# RFmodule.net
KiCad netlist of a schematic drawn in EAGLE
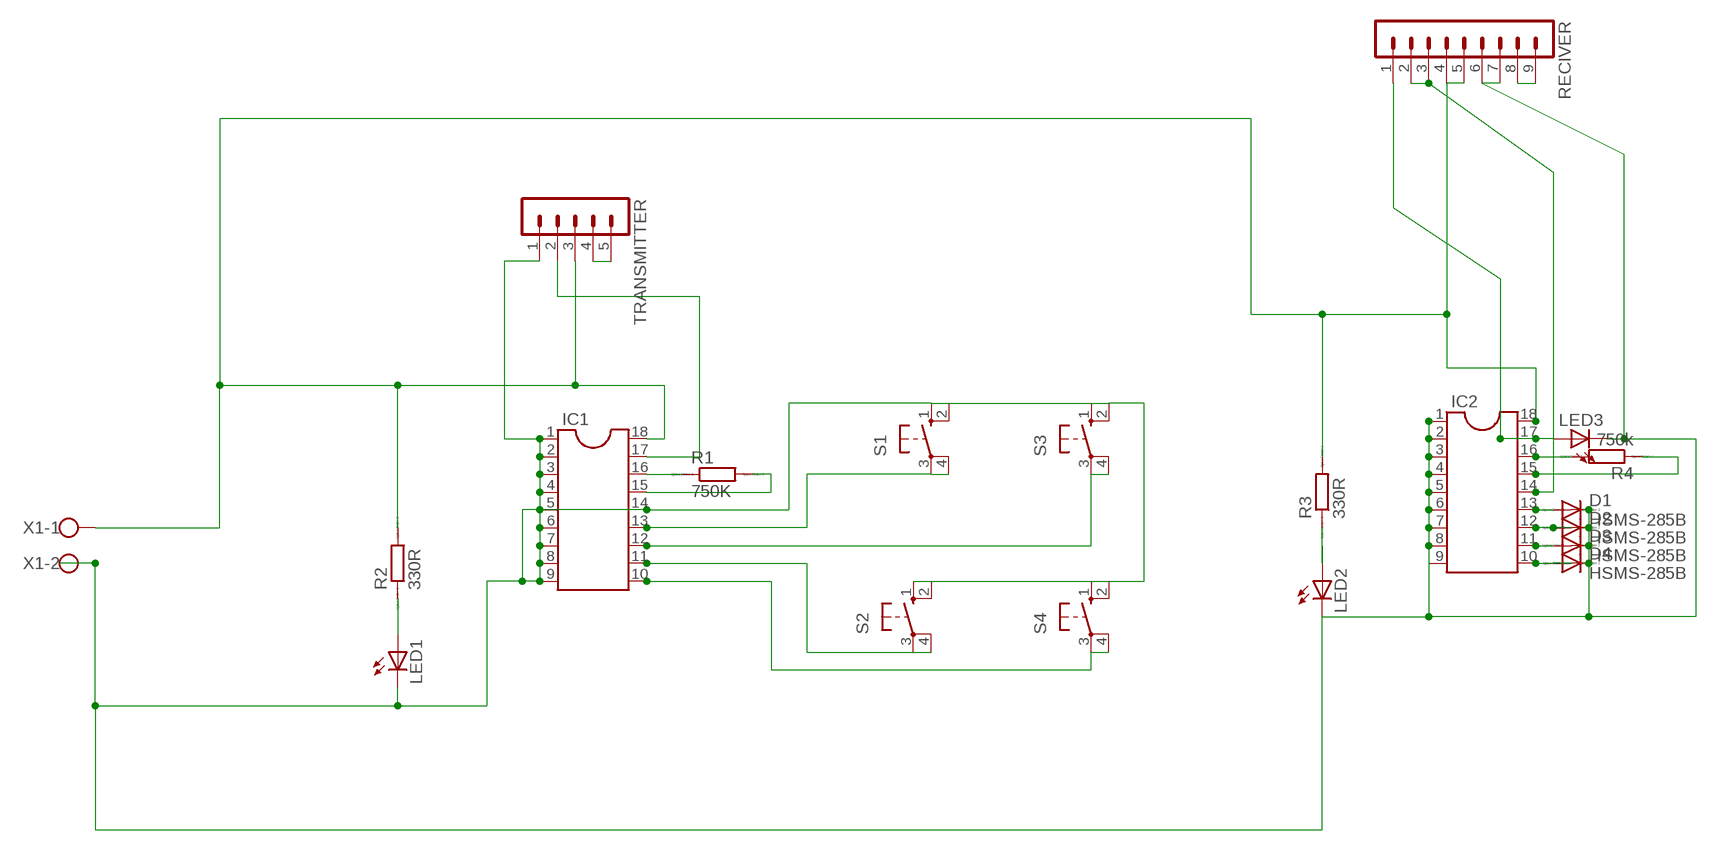
[diagram p0: schematic, sheet 1]

(export (version "E")
  (design (tool "Eeschema 10.0.6"))
  (components
    (comp (ref "D1")
      (value "HSMS-285B")
      (footprint "eagle-import:SOT323")
      (libsource (lib "eagle-import") (part "HSMS-285B"))
    )
    (comp (ref "D2")
      (value "HSMS-285B")
      (footprint "eagle-import:SOT323")
      (libsource (lib "eagle-import") (part "HSMS-285B"))
    )
    (comp (ref "D3")
      (value "HSMS-285B")
      (footprint "eagle-import:SOT323")
      (libsource (lib "eagle-import") (part "HSMS-285B"))
    )
    (comp (ref "D4")
      (value "HSMS-285B")
      (footprint "eagle-import:SOT323")
      (libsource (lib "eagle-import") (part "HSMS-285B"))
    )
    (comp (ref "IC1")
      (value "DIL18")
      (footprint "eagle-import:DIL18")
      (libsource (lib "eagle-import") (part "DIL18"))
    )
    (comp (ref "IC2")
      (value "DIL18")
      (footprint "eagle-import:DIL18")
      (libsource (lib "eagle-import") (part "DIL18"))
    )
    (comp (ref "LED1")
      (value "LED5MM")
      (footprint "eagle-import:LED5MM")
      (libsource (lib "eagle-import") (part "LED5MM"))
    )
    (comp (ref "LED2")
      (value "LED5MM")
      (footprint "eagle-import:LED5MM")
      (libsource (lib "eagle-import") (part "LED5MM"))
    )
    (comp (ref "LED3")
      (value "LED5MM")
      (footprint "eagle-import:LED5MM")
      (libsource (lib "eagle-import") (part "LED5MM"))
    )
    (comp (ref "R1")
      (value "750K")
      (footprint "eagle-import:0207_10")
      (libsource (lib "eagle-import") (part "R0207/10"))
    )
    (comp (ref "R2")
      (value "330R")
      (footprint "eagle-import:0207_10")
      (libsource (lib "eagle-import") (part "R0207/10"))
    )
    (comp (ref "R3")
      (value "330R")
      (footprint "eagle-import:0204_7")
      (libsource (lib "eagle-import") (part "R0204/7"))
    )
    (comp (ref "R4")
      (value "750k")
      (footprint "eagle-import:0204_7")
      (libsource (lib "eagle-import") (part "R0204/7"))
    )
    (comp (ref "RECIVER")
      (value "MA09-1")
      (footprint "eagle-import:MA09-1")
      (libsource (lib "eagle-import") (part "MA09-1"))
    )
    (comp (ref "S1")
      (value "10-XX")
      (footprint "eagle-import:B3F-10XX")
      (fields (field (name "MPN") "B3F-1000"))
      (libsource (lib "eagle-import") (part "10-XX"))
    )
    (comp (ref "S2")
      (value "10-XX")
      (footprint "eagle-import:B3F-10XX")
      (fields (field (name "MPN") "B3F-1000"))
      (libsource (lib "eagle-import") (part "10-XX"))
    )
    (comp (ref "S3")
      (value "10-XX")
      (footprint "eagle-import:B3F-10XX")
      (fields (field (name "MPN") "B3F-1000"))
      (libsource (lib "eagle-import") (part "10-XX"))
    )
    (comp (ref "S4")
      (value "10-XX")
      (footprint "eagle-import:B3F-10XX")
      (fields (field (name "MPN") "B3F-1000"))
      (libsource (lib "eagle-import") (part "10-XX"))
    )
    (comp (ref "TRANSMITTER")
      (value "MA05-1")
      (footprint "eagle-import:MA05-1")
      (libsource (lib "eagle-import") (part "MA05-1"))
    )
    (comp (ref "X1")
      (value "W237-102")
      (footprint "eagle-import:W237-102")
      (fields (field (name "MPN") "237-102"))
      (libsource (lib "eagle-import") (part "W237-102"))
    )
  )
  (nets
    (net (code "1") (name "Net-(D1-A)") (class "Default")
      (node (ref "D1") (pin "1") (pinfunction "A_1") (pintype "passive"))
      (node (ref "IC2") (pin "13") (pinfunction "13_13") (pintype "passive"))
    )
    (net (code "2") (name "Net-(D1-C)") (class "Default")
      (node (ref "D1") (pin "3") (pinfunction "C_3") (pintype "passive"))
      (node (ref "D2") (pin "3") (pinfunction "C_3") (pintype "passive"))
      (node (ref "D3") (pin "3") (pinfunction "C_3") (pintype "passive"))
      (node (ref "D4") (pin "3") (pinfunction "C_3") (pintype "passive"))
      (node (ref "IC1") (pin "1") (pinfunction "1_1") (pintype "passive"))
      (node (ref "IC1") (pin "14") (pinfunction "14_14") (pintype "passive"))
      (node (ref "IC1") (pin "2") (pinfunction "2_2") (pintype "passive"))
      (node (ref "IC1") (pin "3") (pinfunction "3_3") (pintype "passive"))
      (node (ref "IC1") (pin "4") (pinfunction "4_4") (pintype "passive"))
      (node (ref "IC1") (pin "5") (pinfunction "5_5") (pintype "passive"))
      (node (ref "IC1") (pin "6") (pinfunction "6_6") (pintype "passive"))
      (node (ref "IC1") (pin "7") (pinfunction "7_7") (pintype "passive"))
      (node (ref "IC1") (pin "8") (pinfunction "8_8") (pintype "passive"))
      (node (ref "IC1") (pin "9") (pinfunction "9_9") (pintype "passive"))
      (node (ref "IC2") (pin "1") (pinfunction "1_1") (pintype "passive"))
      (node (ref "IC2") (pin "2") (pinfunction "2_2") (pintype "passive"))
      (node (ref "IC2") (pin "3") (pinfunction "3_3") (pintype "passive"))
      (node (ref "IC2") (pin "4") (pinfunction "4_4") (pintype "passive"))
      (node (ref "IC2") (pin "5") (pinfunction "5_5") (pintype "passive"))
      (node (ref "IC2") (pin "6") (pinfunction "6_6") (pintype "passive"))
      (node (ref "IC2") (pin "7") (pinfunction "7_7") (pintype "passive"))
      (node (ref "IC2") (pin "8") (pinfunction "8_8") (pintype "passive"))
      (node (ref "IC2") (pin "9") (pinfunction "9_9") (pintype "passive"))
      (node (ref "LED1") (pin "K") (pinfunction "C_K") (pintype "passive"))
      (node (ref "LED2") (pin "K") (pinfunction "C_K") (pintype "passive"))
      (node (ref "LED3") (pin "K") (pinfunction "C_K") (pintype "passive"))
      (node (ref "RECIVER") (pin "6") (pinfunction "6_6") (pintype "passive"))
      (node (ref "RECIVER") (pin "7") (pinfunction "7_7") (pintype "passive"))
      (node (ref "S1") (pin "1") (pinfunction "S_1") (pintype "passive"))
      (node (ref "S1") (pin "2") (pinfunction "S1_2") (pintype "passive"))
      (node (ref "S2") (pin "1") (pinfunction "S_1") (pintype "passive"))
      (node (ref "S2") (pin "2") (pinfunction "S1_2") (pintype "passive"))
      (node (ref "S3") (pin "1") (pinfunction "S_1") (pintype "passive"))
      (node (ref "S3") (pin "2") (pinfunction "S1_2") (pintype "passive"))
      (node (ref "S4") (pin "1") (pinfunction "S_1") (pintype "passive"))
      (node (ref "S4") (pin "2") (pinfunction "S1_2") (pintype "passive"))
      (node (ref "TRANSMITTER") (pin "1") (pinfunction "1_1") (pintype "passive"))
      (node (ref "X1") (pin "2") (pinfunction "KL_2") (pintype "passive"))
    )
    (net (code "3") (name "Net-(D2-A)") (class "Default")
      (node (ref "D2") (pin "1") (pinfunction "A_1") (pintype "passive"))
      (node (ref "IC2") (pin "12") (pinfunction "12_12") (pintype "passive"))
    )
    (net (code "4") (name "Net-(D3-A)") (class "Default")
      (node (ref "D3") (pin "1") (pinfunction "A_1") (pintype "passive"))
      (node (ref "IC2") (pin "11") (pinfunction "11_11") (pintype "passive"))
    )
    (net (code "5") (name "Net-(D4-A)") (class "Default")
      (node (ref "D4") (pin "1") (pinfunction "A_1") (pintype "passive"))
      (node (ref "IC2") (pin "10") (pinfunction "10_10") (pintype "passive"))
    )
    (net (code "6") (name "Net-(IC1-Pad15)") (class "Default")
      (node (ref "IC1") (pin "15") (pinfunction "15_15") (pintype "passive"))
      (node (ref "R1") (pin "2") (pinfunction "2_2") (pintype "passive"))
    )
    (net (code "7") (name "Net-(IC1-Pad16)") (class "Default")
      (node (ref "IC1") (pin "16") (pinfunction "16_16") (pintype "passive"))
      (node (ref "R1") (pin "1") (pinfunction "1_1") (pintype "passive"))
    )
    (net (code "8") (name "Net-(IC1-Pad17)") (class "Default")
      (node (ref "IC1") (pin "17") (pinfunction "17_17") (pintype "passive"))
      (node (ref "TRANSMITTER") (pin "2") (pinfunction "2_2") (pintype "passive"))
    )
    (net (code "9") (name "Net-(IC2-Pad14)") (class "Default")
      (node (ref "IC2") (pin "14") (pinfunction "14_14") (pintype "passive"))
      (node (ref "RECIVER") (pin "2") (pinfunction "2_2") (pintype "passive"))
      (node (ref "RECIVER") (pin "3") (pinfunction "3_3") (pintype "passive"))
    )
    (net (code "10") (name "Net-(IC2-Pad15)") (class "Default")
      (node (ref "IC2") (pin "15") (pinfunction "15_15") (pintype "passive"))
      (node (ref "R4") (pin "1") (pinfunction "1_1") (pintype "passive"))
    )
    (net (code "11") (name "Net-(IC2-Pad16)") (class "Default")
      (node (ref "IC2") (pin "16") (pinfunction "16_16") (pintype "passive"))
      (node (ref "R4") (pin "2") (pinfunction "2_2") (pintype "passive"))
    )
    (net (code "12") (name "Net-(IC2-Pad17)") (class "Default")
      (node (ref "IC2") (pin "17") (pinfunction "17_17") (pintype "passive"))
      (node (ref "LED3") (pin "A") (pinfunction "A_A") (pintype "passive"))
      (node (ref "RECIVER") (pin "1") (pinfunction "1_1") (pintype "passive"))
    )
    (net (code "13") (name "Net-(LED1-PadA)") (class "Default")
      (node (ref "LED1") (pin "A") (pinfunction "A_A") (pintype "passive"))
      (node (ref "R2") (pin "1") (pinfunction "1_1") (pintype "passive"))
    )
    (net (code "14") (name "Net-(LED2-PadA)") (class "Default")
      (node (ref "LED2") (pin "A") (pinfunction "A_A") (pintype "passive"))
      (node (ref "R3") (pin "1") (pinfunction "1_1") (pintype "passive"))
    )
    (net (code "15") (name "Net-(RECIVER-Pad8)") (class "Default")
      (node (ref "RECIVER") (pin "8") (pinfunction "8_8") (pintype "passive"))
      (node (ref "RECIVER") (pin "9") (pinfunction "9_9") (pintype "passive"))
    )
    (net (code "16") (name "Net-(S1-P)") (class "Default")
      (node (ref "IC1") (pin "13") (pinfunction "13_13") (pintype "passive"))
      (node (ref "S1") (pin "3") (pinfunction "P_3") (pintype "passive"))
      (node (ref "S1") (pin "4") (pinfunction "P1_4") (pintype "passive"))
    )
    (net (code "17") (name "Net-(S2-P)") (class "Default")
      (node (ref "IC1") (pin "11") (pinfunction "11_11") (pintype "passive"))
      (node (ref "S2") (pin "3") (pinfunction "P_3") (pintype "passive"))
      (node (ref "S2") (pin "4") (pinfunction "P1_4") (pintype "passive"))
    )
    (net (code "18") (name "Net-(S3-P)") (class "Default")
      (node (ref "IC1") (pin "12") (pinfunction "12_12") (pintype "passive"))
      (node (ref "S3") (pin "3") (pinfunction "P_3") (pintype "passive"))
      (node (ref "S3") (pin "4") (pinfunction "P1_4") (pintype "passive"))
    )
    (net (code "19") (name "Net-(S4-P)") (class "Default")
      (node (ref "IC1") (pin "10") (pinfunction "10_10") (pintype "passive"))
      (node (ref "S4") (pin "3") (pinfunction "P_3") (pintype "passive"))
      (node (ref "S4") (pin "4") (pinfunction "P1_4") (pintype "passive"))
    )
    (net (code "20") (name "Net-(TRANSMITTER-Pad4)") (class "Default")
      (node (ref "TRANSMITTER") (pin "4") (pinfunction "4_4") (pintype "passive"))
      (node (ref "TRANSMITTER") (pin "5") (pinfunction "5_5") (pintype "passive"))
    )
    (net (code "21") (name "Net-(X1A-KL)") (class "Default")
      (node (ref "IC1") (pin "18") (pinfunction "18_18") (pintype "passive"))
      (node (ref "IC2") (pin "18") (pinfunction "18_18") (pintype "passive"))
      (node (ref "R2") (pin "2") (pinfunction "2_2") (pintype "passive"))
      (node (ref "R3") (pin "2") (pinfunction "2_2") (pintype "passive"))
      (node (ref "RECIVER") (pin "4") (pinfunction "4_4") (pintype "passive"))
      (node (ref "RECIVER") (pin "5") (pinfunction "5_5") (pintype "passive"))
      (node (ref "TRANSMITTER") (pin "3") (pinfunction "3_3") (pintype "passive"))
      (node (ref "X1") (pin "1") (pinfunction "KL_1") (pintype "passive"))
    )
  )
)
